# sVNS_16chan.net
KiCad netlist of a schematic drawn in EAGLE
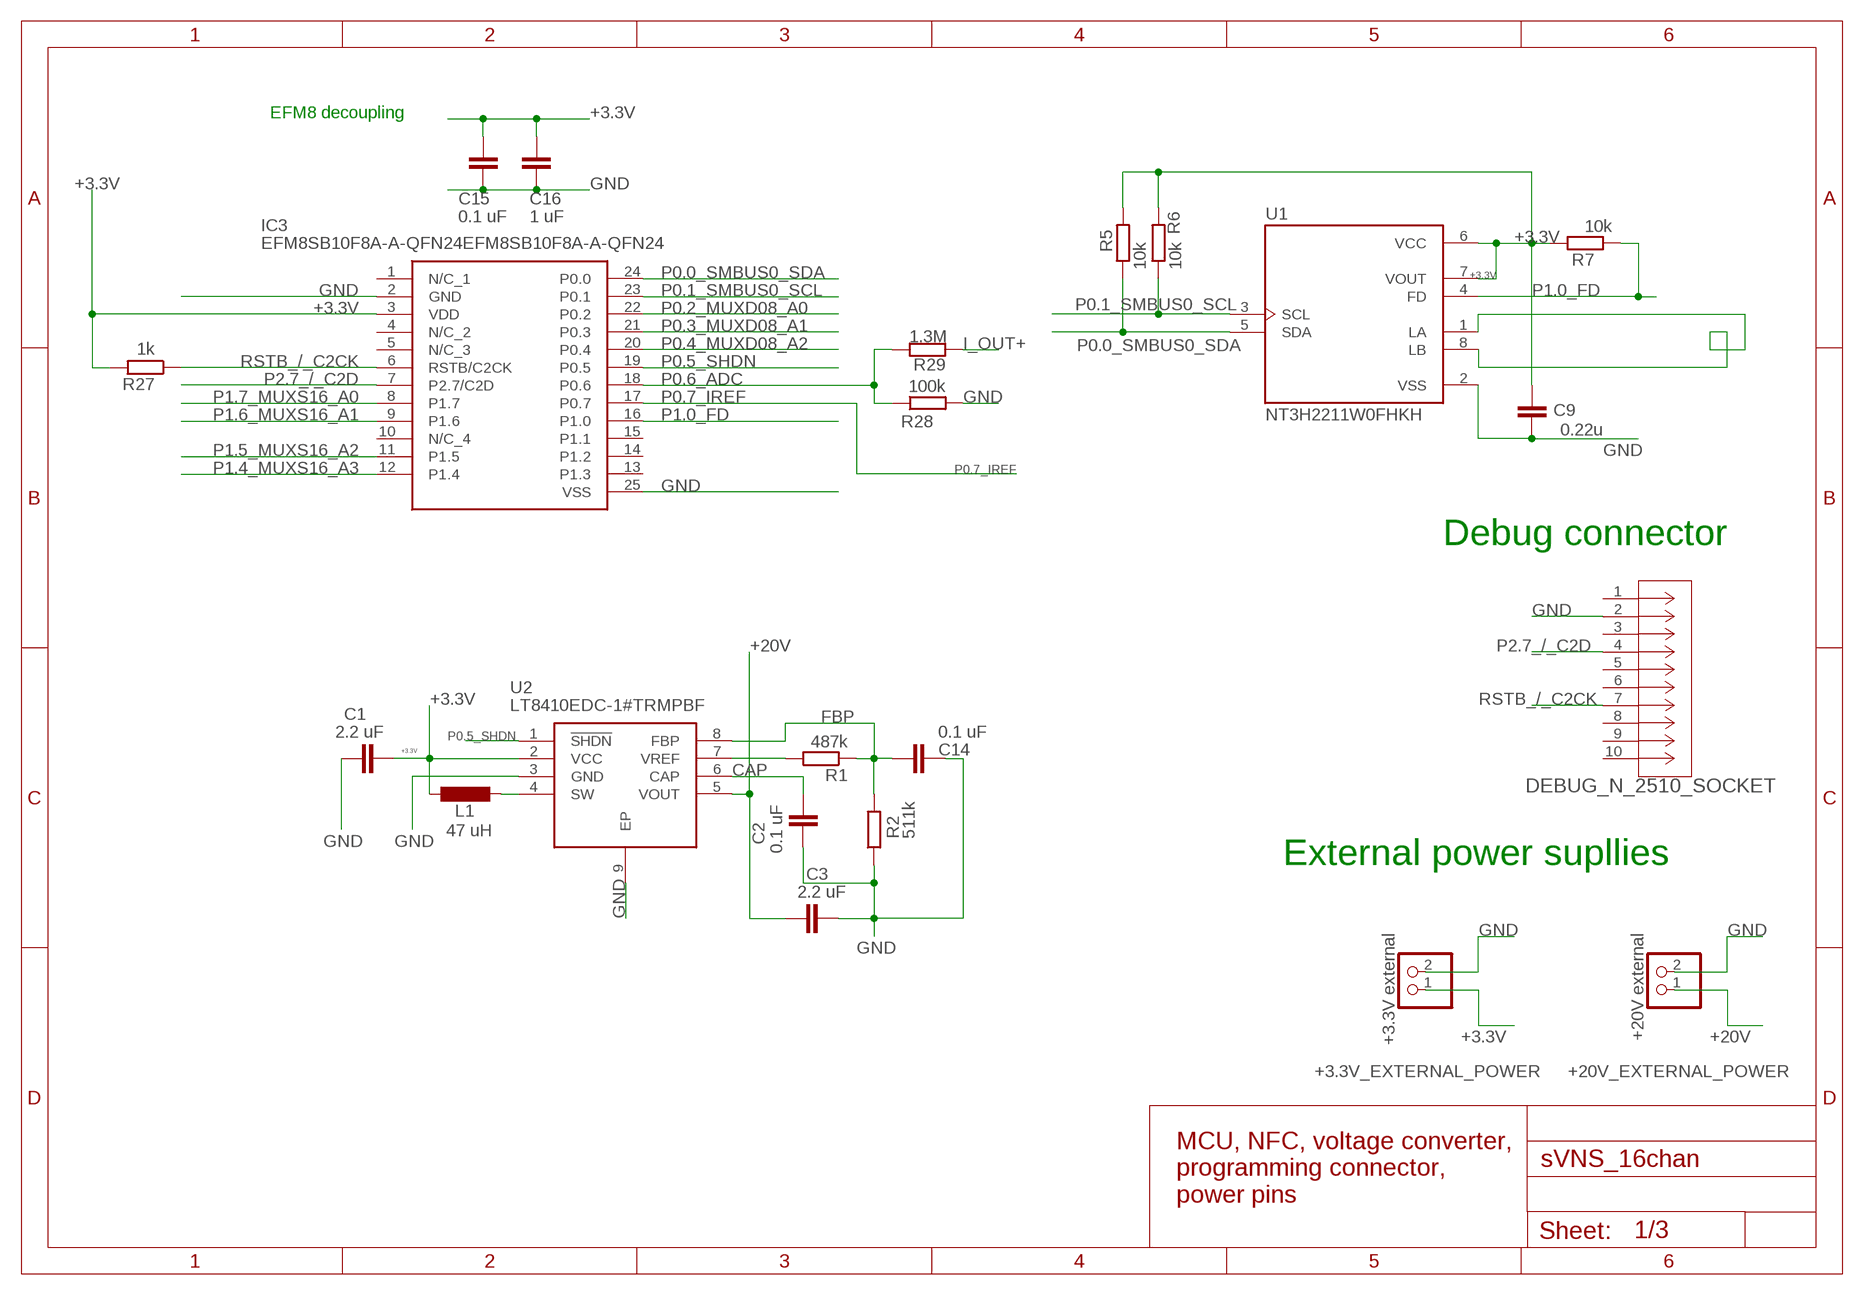
[diagram p0: schematic, sheet 1]
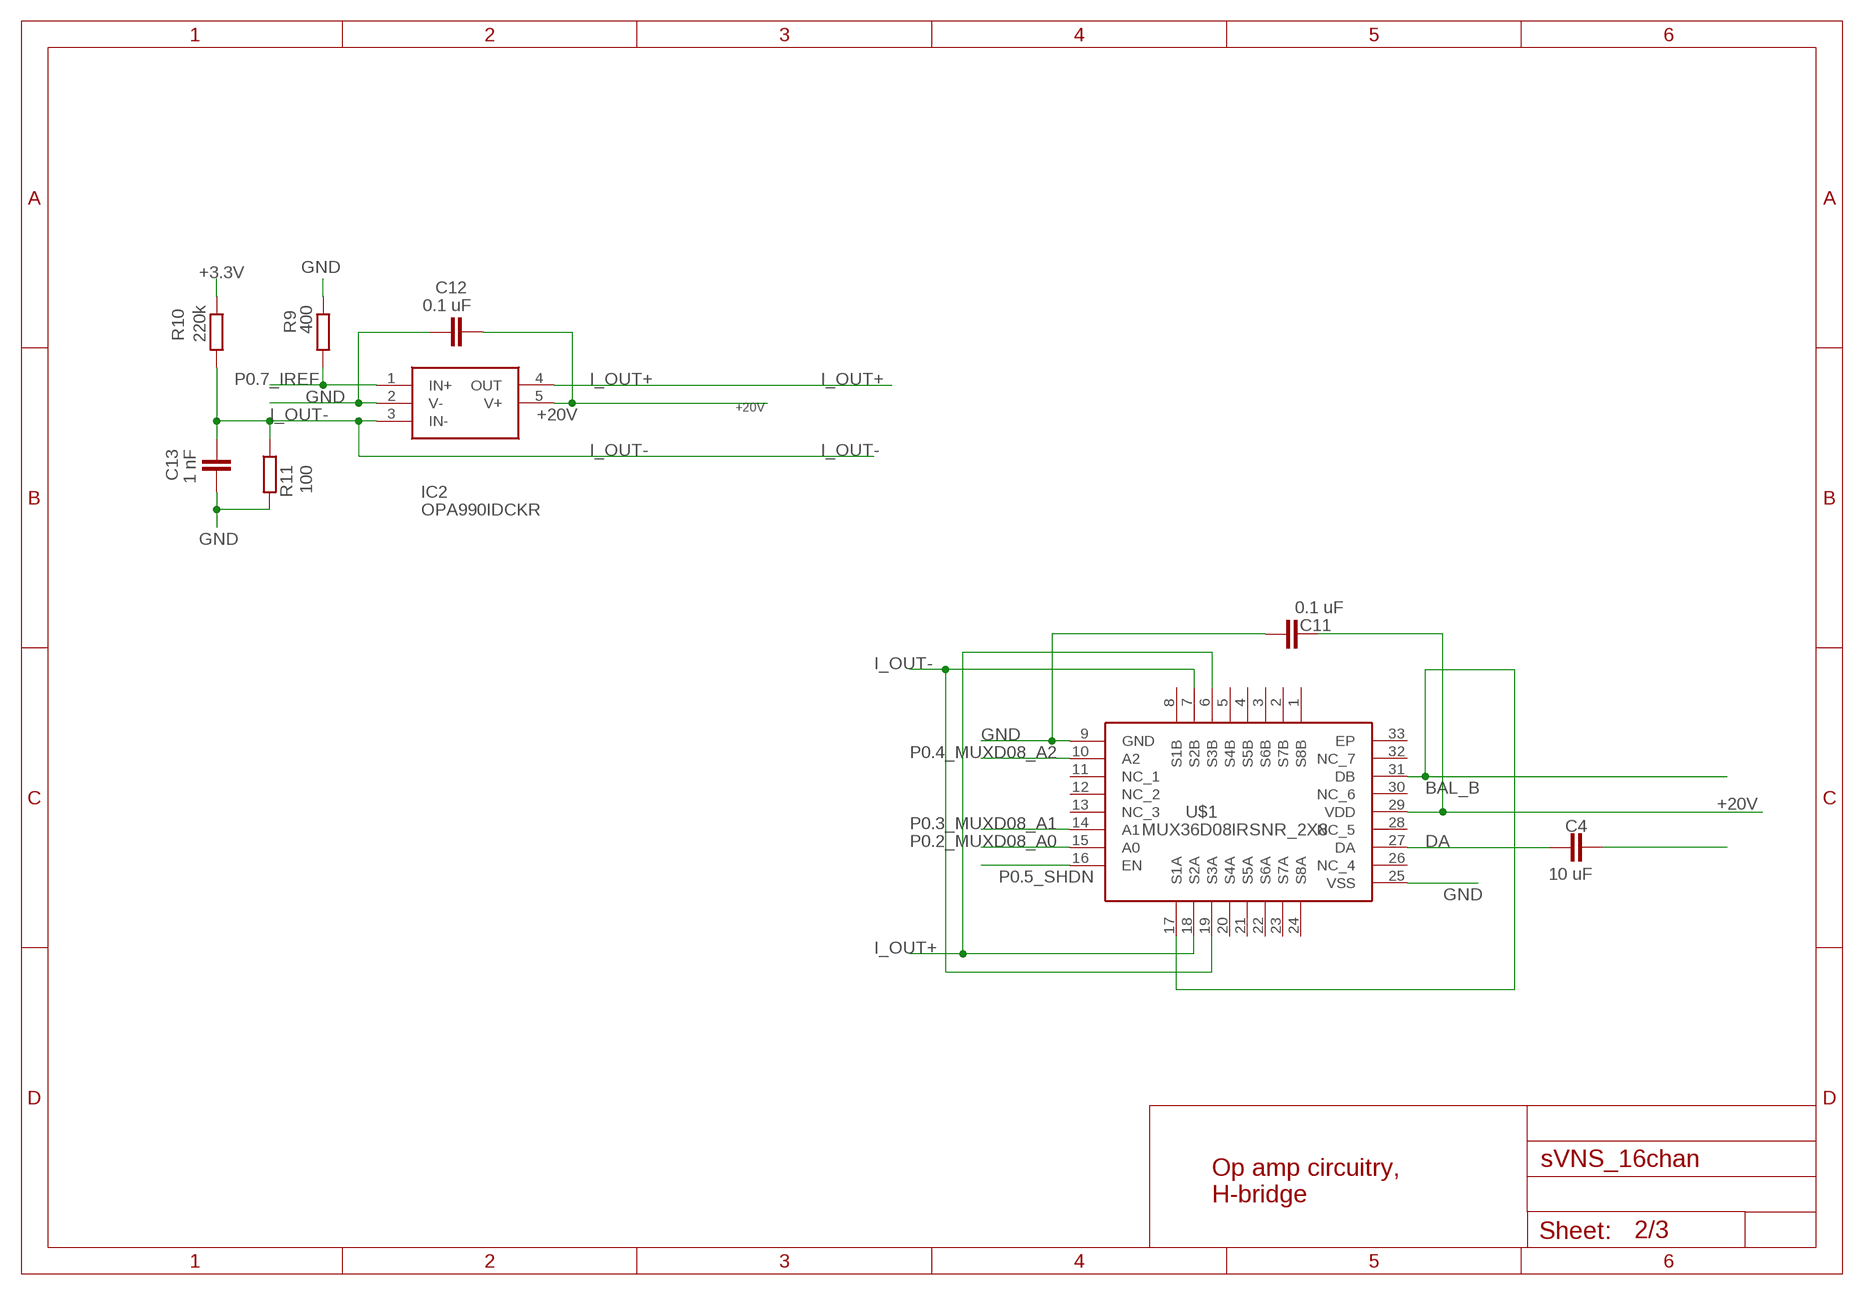
[diagram p1: schematic, sheet 2]
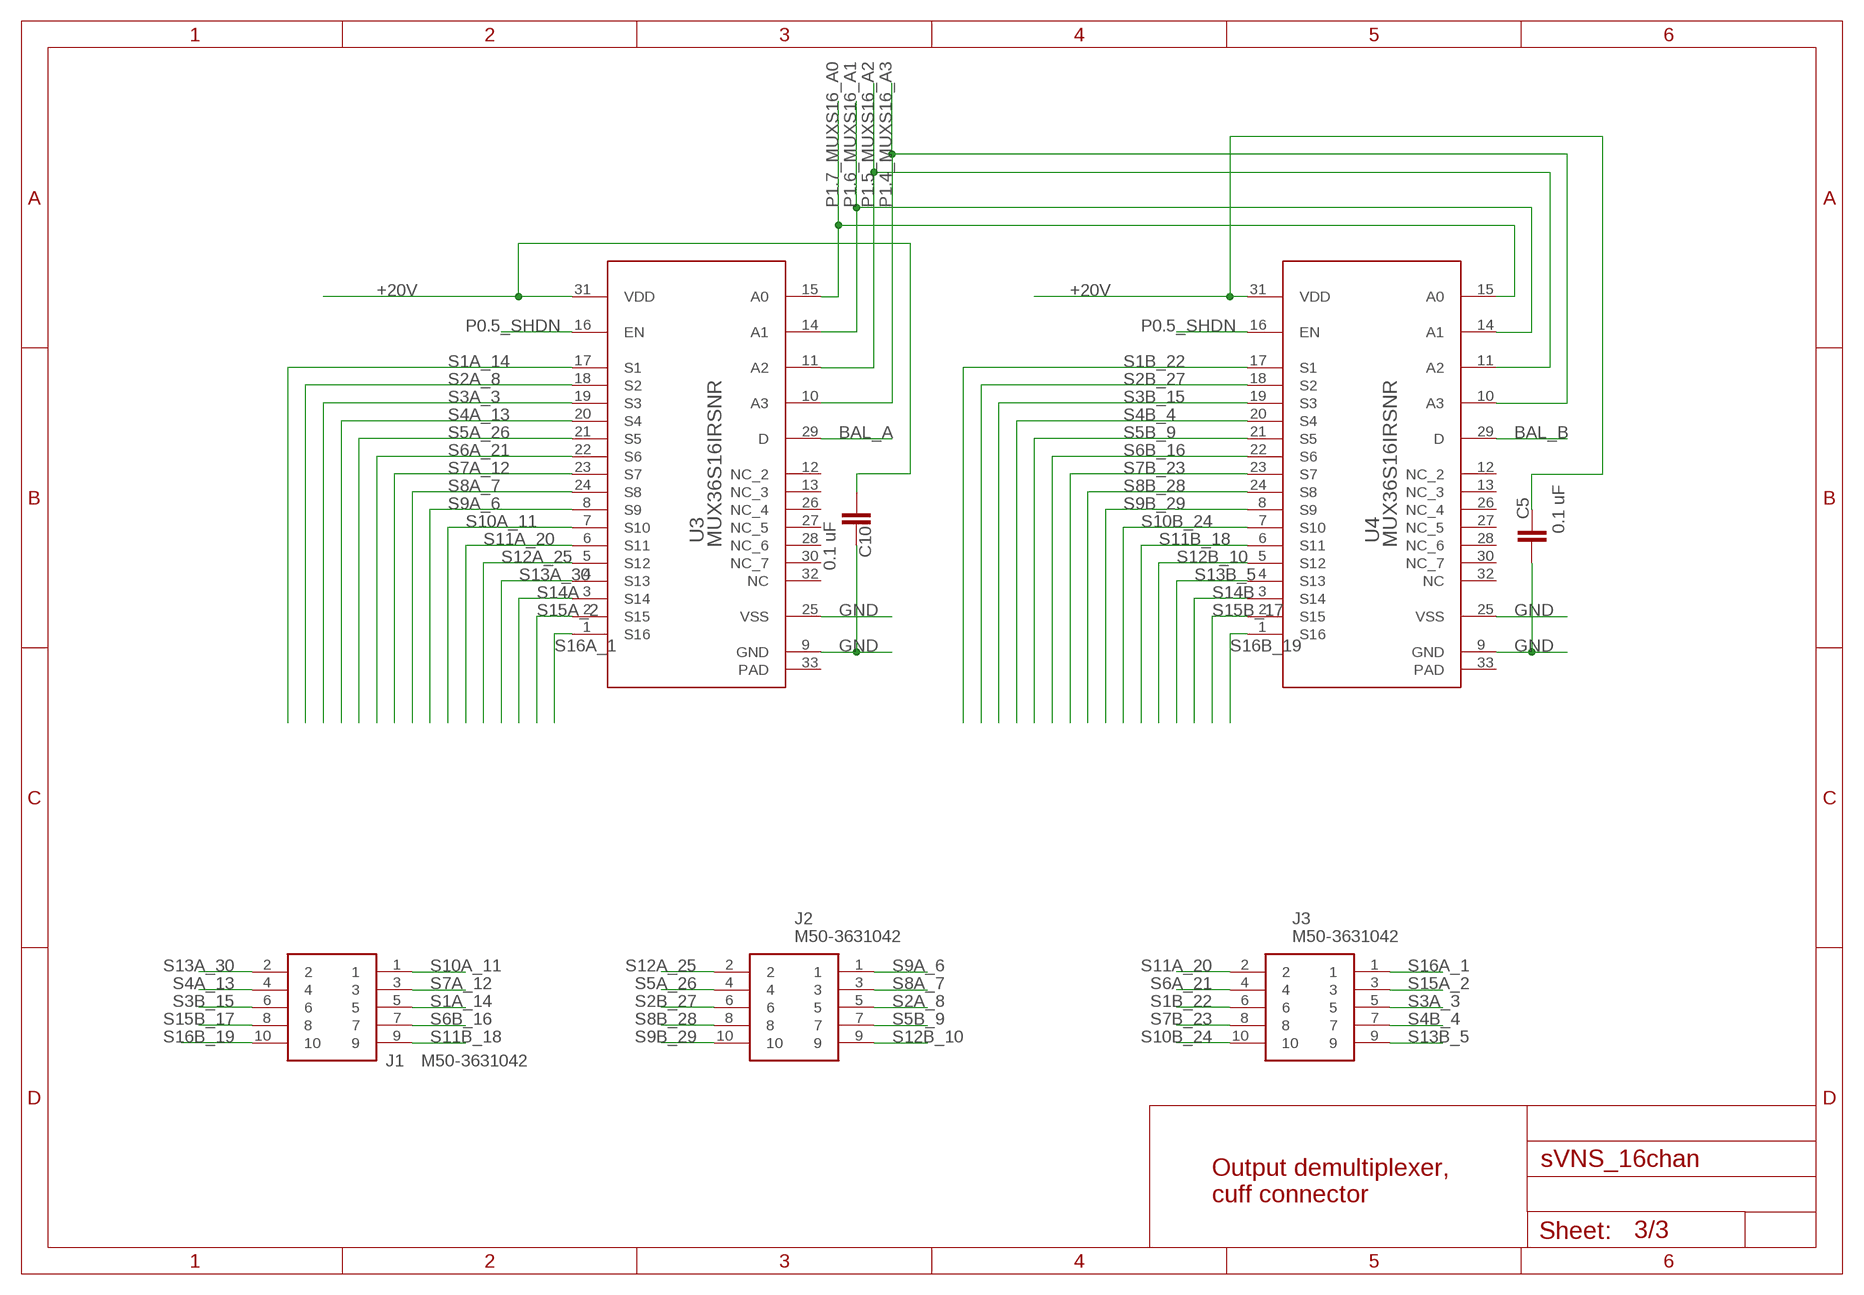
[diagram p2: schematic, sheet 3]

(export (version "E")
  (design (tool "Eeschema 10.0.6"))
  (components
    (comp (ref "C4")
      (value "10 uF")
      (footprint "eagle-import:C0603")
      (libsource (lib "eagle-import") (part "C-EUC0603"))
    )
    (comp (ref "C11")
      (value "0.1 uF")
      (footprint "eagle-import:C0603")
      (libsource (lib "eagle-import") (part "C-EUC0603"))
    )
    (comp (ref "C12")
      (value "0.1 uF")
      (footprint "eagle-import:C0603")
      (libsource (lib "eagle-import") (part "C-EUC0603"))
    )
    (comp (ref "C13")
      (value "1 nF")
      (footprint "eagle-import:C0603")
      (libsource (lib "eagle-import") (part "C-EUC0603"))
    )
    (comp (ref "IC2")
      (value "OPA990IDCKR")
      (footprint "eagle-import:SOT65P210X110-5N")
      (fields (field (name "MOUSER_PART_NUMBER") "595-OPA990IDCKR"))
      (libsource (lib "eagle-import") (part "OPA990IDCKR"))
    )
    (comp (ref "R9")
      (value "400")
      (footprint "eagle-import:R0603")
      (libsource (lib "eagle-import") (part "R-EU_R0603"))
    )
    (comp (ref "R10")
      (value "220k")
      (footprint "eagle-import:R0603")
      (libsource (lib "eagle-import") (part "R-EU_R0603"))
    )
    (comp (ref "R11")
      (value "100")
      (footprint "eagle-import:R0603")
      (libsource (lib "eagle-import") (part "R-EU_R0603"))
    )
    (comp (ref "U$1")
      (value "MUX36D08IRSNR_2X8")
      (footprint "eagle-import:QFN40P400X400X80-33N_2X8")
      (libsource (lib "eagle-import") (part "MUX36D08IRSNR_2X8"))
    )
    (comp (ref "+3.3V_EXTERNAL_POWER")
      (value "+3.3V external")
      (footprint "eagle-import:1X02")
      (libsource (lib "eagle-import") (part "PINHD-1X2"))
    )
    (comp (ref "+20V_EXTERNAL_POWER")
      (value "+20V external")
      (footprint "eagle-import:1X02")
      (libsource (lib "eagle-import") (part "PINHD-1X2"))
    )
    (comp (ref "C1")
      (value "2.2 uF")
      (footprint "eagle-import:C0603")
      (libsource (lib "eagle-import") (part "C-EUC0603"))
    )
    (comp (ref "C2")
      (value "0.1 uF")
      (footprint "eagle-import:C0603")
      (libsource (lib "eagle-import") (part "C-EUC0603"))
    )
    (comp (ref "C3")
      (value "2.2 uF")
      (footprint "eagle-import:C0603")
      (libsource (lib "eagle-import") (part "C-EUC0603"))
    )
    (comp (ref "C9")
      (value "0.22u")
      (footprint "eagle-import:C0603")
      (libsource (lib "eagle-import") (part "C-EUC0603"))
    )
    (comp (ref "C14")
      (value "0.1 uF")
      (footprint "eagle-import:C0603")
      (libsource (lib "eagle-import") (part "C-EUC0603"))
    )
    (comp (ref "C15")
      (value "0.1 uF")
      (footprint "eagle-import:C0603")
      (libsource (lib "eagle-import") (part "C-EUC0603"))
    )
    (comp (ref "C16")
      (value "1 uF")
      (footprint "eagle-import:C0603")
      (libsource (lib "eagle-import") (part "C-EUC0603"))
    )
    (comp (ref "DEBUG_N_2510_SOCKET")
      (value "N2510-6002RB")
      (footprint "eagle-import:CONN_6002RB_3MM")
      (fields (field (name "COPYRIGHT") "Copyright (C) 2021 Ultra Librarian. All rights reserved."))
      (libsource (lib "eagle-import") (part "N2510-6002RB"))
    )
    (comp (ref "IC3")
      (value "EFM8SB10F8A-A-QFN24EFM8SB10F8A-A-QFN24")
      (footprint "eagle-import:QFN50P400X400X80-25T245N")
      (libsource (lib "eagle-import") (part "EFM8SB10F8A-A-QFN24EFM8SB10F8A-A-QFN24"))
    )
    (comp (ref "L1")
      (value "47 uH")
      (footprint "eagle-import:0603PS-473KRC")
      (libsource (lib "eagle-import") (part "0603PS-473KRC0603PS"))
    )
    (comp (ref "R1")
      (value "487k")
      (footprint "eagle-import:R0603")
      (libsource (lib "eagle-import") (part "R-EU_R0603"))
    )
    (comp (ref "R2")
      (value "511k")
      (footprint "eagle-import:R0603")
      (libsource (lib "eagle-import") (part "R-EU_R0603"))
    )
    (comp (ref "R5")
      (value "10k")
      (footprint "eagle-import:R0603")
      (libsource (lib "eagle-import") (part "R-EU_R0603"))
    )
    (comp (ref "R6")
      (value "10k")
      (footprint "eagle-import:R0603")
      (libsource (lib "eagle-import") (part "R-EU_R0603"))
    )
    (comp (ref "R7")
      (value "10k")
      (footprint "eagle-import:R0603")
      (libsource (lib "eagle-import") (part "R-EU_R0603"))
    )
    (comp (ref "R27")
      (value "1k")
      (footprint "eagle-import:R0603")
      (libsource (lib "eagle-import") (part "R-EU_R0603"))
    )
    (comp (ref "R28")
      (value "100k")
      (footprint "eagle-import:R0603")
      (libsource (lib "eagle-import") (part "R-EU_R0603"))
    )
    (comp (ref "R29")
      (value "1.3M")
      (footprint "eagle-import:R0603")
      (libsource (lib "eagle-import") (part "R-EU_R0603"))
    )
    (comp (ref "U1")
      (value "NT3H2211W0FHKH")
      (footprint "eagle-import:IC_NT3H2211W0FHKH")
      (fields (field (name "MF") "NXP USA"))
      (libsource (lib "eagle-import") (part "NT3H2211W0FHKH"))
    )
    (comp (ref "U2")
      (value "LT8410EDC-1#TRMPBF")
      (footprint "eagle-import:SON45P200X200X80-9N")
      (fields (field (name "MOUSER_PART_NUMBER") "584-8410EDC-1TRMPBF"))
      (libsource (lib "eagle-import") (part "LT8410EDC-1#TRMPBF"))
    )
    (comp (ref "C5")
      (value "0.1 uF")
      (footprint "eagle-import:C0603")
      (libsource (lib "eagle-import") (part "C-EUC0603"))
    )
    (comp (ref "C10")
      (value "0.1 uF")
      (footprint "eagle-import:C0603")
      (libsource (lib "eagle-import") (part "C-EUC0603"))
    )
    (comp (ref "J1")
      (value "M50-3631042")
      (footprint "eagle-import:M503631042")
      (fields (field (name "MOUSER_PART_NUMBER") "855-M50-3631042"))
      (libsource (lib "eagle-import") (part "M50-3631042"))
    )
    (comp (ref "J2")
      (value "M50-3631042")
      (footprint "eagle-import:M503631042")
      (fields (field (name "MOUSER_PART_NUMBER") "855-M50-3631042"))
      (libsource (lib "eagle-import") (part "M50-3631042"))
    )
    (comp (ref "J3")
      (value "M50-3631042")
      (footprint "eagle-import:M503631042")
      (fields (field (name "MOUSER_PART_NUMBER") "855-M50-3631042"))
      (libsource (lib "eagle-import") (part "M50-3631042"))
    )
    (comp (ref "U3")
      (value "MUX36S16IRSNR")
      (footprint "eagle-import:RSN0032B")
      (fields (field (name "COPYRIGHT") "Copyright (C) 2022 Ultra Librarian. All rights reserved."))
      (libsource (lib "eagle-import") (part "MUX36S16IRSNR"))
    )
    (comp (ref "U4")
      (value "MUX36S16IRSNR")
      (footprint "eagle-import:RSN0032B")
      (fields (field (name "COPYRIGHT") "Copyright (C) 2022 Ultra Librarian. All rights reserved."))
      (libsource (lib "eagle-import") (part "MUX36S16IRSNR"))
    )
  )
  (nets
    (net (code "1") (name "+3.3V") (class "Default")
      (node (ref "+3.3V_EXTERNAL_POWER") (pin "1") (pinfunction "1_1") (pintype "passive"))
      (node (ref "C1") (pin "2") (pinfunction "2_2") (pintype "passive"))
      (node (ref "C15") (pin "2") (pinfunction "2_2") (pintype "passive"))
      (node (ref "C16") (pin "1") (pinfunction "1_1") (pintype "passive"))
      (node (ref "C9") (pin "1") (pinfunction "1_1") (pintype "passive"))
      (node (ref "IC3") (pin "3") (pinfunction "VDD_3") (pintype "power_in"))
      (node (ref "L1") (pin "P$1") (pinfunction "1_P$1") (pintype "passive"))
      (node (ref "R10") (pin "1") (pinfunction "1_1") (pintype "passive"))
      (node (ref "R27") (pin "2") (pinfunction "2_2") (pintype "passive"))
      (node (ref "R5") (pin "2") (pinfunction "2_2") (pintype "passive"))
      (node (ref "R6") (pin "2") (pinfunction "2_2") (pintype "passive"))
      (node (ref "R7") (pin "2") (pinfunction "2_2") (pintype "passive"))
      (node (ref "U1") (pin "6") (pinfunction "VCC_6") (pintype "power_in"))
      (node (ref "U1") (pin "7") (pinfunction "VOUT_7") (pintype "output"))
      (node (ref "U2") (pin "2") (pinfunction "VCC_2") (pintype "bidirectional"))
    )
    (net (code "2") (name "+20V") (class "Default")
      (node (ref "+20V_EXTERNAL_POWER") (pin "1") (pinfunction "1_1") (pintype "passive"))
      (node (ref "C10") (pin "1") (pinfunction "1_1") (pintype "passive"))
      (node (ref "C11") (pin "2") (pinfunction "2_2") (pintype "passive"))
      (node (ref "C12") (pin "1") (pinfunction "1_1") (pintype "passive"))
      (node (ref "C3") (pin "1") (pinfunction "1_1") (pintype "passive"))
      (node (ref "C5") (pin "2") (pinfunction "2_2") (pintype "passive"))
      (node (ref "IC2") (pin "5") (pinfunction "V+_5") (pintype "bidirectional"))
      (node (ref "U$1") (pin "29") (pinfunction "VDD_29") (pintype "bidirectional"))
      (node (ref "U2") (pin "5") (pinfunction "VOUT_5") (pintype "bidirectional"))
      (node (ref "U3") (pin "31") (pinfunction "VDD_31") (pintype "power_in"))
      (node (ref "U4") (pin "31") (pinfunction "VDD_31") (pintype "power_in"))
    )
    (net (code "3") (name "BAL_A") (class "Default")
      (node (ref "C4") (pin "2") (pinfunction "2_2") (pintype "passive"))
      (node (ref "U3") (pin "29") (pinfunction "D_29") (pintype "bidirectional"))
    )
    (net (code "4") (name "BAL_B") (class "Default")
      (node (ref "U$1") (pin "17") (pinfunction "S1A_17") (pintype "bidirectional"))
      (node (ref "U$1") (pin "31") (pinfunction "DB_31") (pintype "bidirectional"))
      (node (ref "U4") (pin "29") (pinfunction "D_29") (pintype "bidirectional"))
    )
    (net (code "5") (name "CAP") (class "Default")
      (node (ref "C2") (pin "2") (pinfunction "2_2") (pintype "passive"))
      (node (ref "U2") (pin "6") (pinfunction "CAP_6") (pintype "bidirectional"))
    )
    (net (code "6") (name "DA") (class "Default")
      (node (ref "C4") (pin "1") (pinfunction "1_1") (pintype "passive"))
      (node (ref "U$1") (pin "27") (pinfunction "DA_27") (pintype "bidirectional"))
    )
    (net (code "7") (name "FBP") (class "Default")
      (node (ref "C14") (pin "2") (pinfunction "2_2") (pintype "passive"))
      (node (ref "R1") (pin "1") (pinfunction "1_1") (pintype "passive"))
      (node (ref "R2") (pin "2") (pinfunction "2_2") (pintype "passive"))
      (node (ref "U2") (pin "8") (pinfunction "FBP_8") (pintype "bidirectional"))
    )
    (net (code "8") (name "GND") (class "Default")
      (node (ref "+20V_EXTERNAL_POWER") (pin "2") (pinfunction "2_2") (pintype "passive"))
      (node (ref "+3.3V_EXTERNAL_POWER") (pin "2") (pinfunction "2_2") (pintype "passive"))
      (node (ref "C1") (pin "1") (pinfunction "1_1") (pintype "passive"))
      (node (ref "C10") (pin "2") (pinfunction "2_2") (pintype "passive"))
      (node (ref "C11") (pin "1") (pinfunction "1_1") (pintype "passive"))
      (node (ref "C12") (pin "2") (pinfunction "2_2") (pintype "passive"))
      (node (ref "C13") (pin "1") (pinfunction "1_1") (pintype "passive"))
      (node (ref "C14") (pin "1") (pinfunction "1_1") (pintype "passive"))
      (node (ref "C15") (pin "1") (pinfunction "1_1") (pintype "passive"))
      (node (ref "C16") (pin "2") (pinfunction "2_2") (pintype "passive"))
      (node (ref "C2") (pin "1") (pinfunction "1_1") (pintype "passive"))
      (node (ref "C3") (pin "2") (pinfunction "2_2") (pintype "passive"))
      (node (ref "C5") (pin "1") (pinfunction "1_1") (pintype "passive"))
      (node (ref "C9") (pin "2") (pinfunction "2_2") (pintype "passive"))
      (node (ref "DEBUG_N_2510_SOCKET") (pin "2") (pinfunction "2_2") (pintype "passive"))
      (node (ref "IC2") (pin "2") (pinfunction "V-_2") (pintype "bidirectional"))
      (node (ref "IC3") (pin "2") (pinfunction "GND_2") (pintype "bidirectional"))
      (node (ref "IC3") (pin "25") (pinfunction "VSS_25") (pintype "bidirectional"))
      (node (ref "R11") (pin "2") (pinfunction "2_2") (pintype "passive"))
      (node (ref "R2") (pin "1") (pinfunction "1_1") (pintype "passive"))
      (node (ref "R28") (pin "2") (pinfunction "2_2") (pintype "passive"))
      (node (ref "R9") (pin "1") (pinfunction "1_1") (pintype "passive"))
      (node (ref "U$1") (pin "25") (pinfunction "VSS_25") (pintype "bidirectional"))
      (node (ref "U$1") (pin "9") (pinfunction "GND_9") (pintype "bidirectional"))
      (node (ref "U1") (pin "2") (pinfunction "VSS_2") (pintype "power_in"))
      (node (ref "U2") (pin "3") (pinfunction "GND_3") (pintype "bidirectional"))
      (node (ref "U2") (pin "9") (pinfunction "EP_9") (pintype "bidirectional"))
      (node (ref "U3") (pin "25") (pinfunction "VSS_25") (pintype "power_in"))
      (node (ref "U3") (pin "9") (pinfunction "GND_9") (pintype "power_in"))
      (node (ref "U4") (pin "25") (pinfunction "VSS_25") (pintype "power_in"))
      (node (ref "U4") (pin "9") (pinfunction "GND_9") (pintype "power_in"))
    )
    (net (code "9") (name "I_OUT+") (class "Default")
      (node (ref "IC2") (pin "4") (pinfunction "OUT_4") (pintype "bidirectional"))
      (node (ref "R29") (pin "1") (pinfunction "1_1") (pintype "passive"))
      (node (ref "U$1") (pin "18") (pinfunction "S2A_18") (pintype "bidirectional"))
      (node (ref "U$1") (pin "6") (pinfunction "S3B_6") (pintype "bidirectional"))
    )
    (net (code "10") (name "I_OUT-") (class "Default")
      (node (ref "C13") (pin "2") (pinfunction "2_2") (pintype "passive"))
      (node (ref "IC2") (pin "3") (pinfunction "IN-_3") (pintype "bidirectional"))
      (node (ref "R10") (pin "2") (pinfunction "2_2") (pintype "passive"))
      (node (ref "R11") (pin "1") (pinfunction "1_1") (pintype "passive"))
      (node (ref "U$1") (pin "19") (pinfunction "S3A_19") (pintype "bidirectional"))
      (node (ref "U$1") (pin "7") (pinfunction "S2B_7") (pintype "bidirectional"))
    )
    (net (code "11") (name "Net-(L1-2)") (class "Default")
      (node (ref "L1") (pin "P$2") (pinfunction "2_P$2") (pintype "passive"))
      (node (ref "U2") (pin "4") (pinfunction "SW_4") (pintype "bidirectional"))
    )
    (net (code "12") (name "Net-(U1-LA)") (class "Default")
      (node (ref "U1") (pin "1") (pinfunction "LA_1") (pintype "bidirectional"))
      (node (ref "U1") (pin "8") (pinfunction "LB_8") (pintype "bidirectional"))
    )
    (net (code "13") (name "Net-(U2-VREF)") (class "Default")
      (node (ref "R1") (pin "2") (pinfunction "2_2") (pintype "passive"))
      (node (ref "U2") (pin "7") (pinfunction "VREF_7") (pintype "bidirectional"))
    )
    (net (code "14") (name "P0.0_SMBUS0_SDA") (class "Default")
      (node (ref "IC3") (pin "24") (pinfunction "P0.0_24") (pintype "bidirectional"))
      (node (ref "R5") (pin "1") (pinfunction "1_1") (pintype "passive"))
      (node (ref "U1") (pin "5") (pinfunction "SDA_5") (pintype "bidirectional"))
    )
    (net (code "15") (name "P0.1_SMBUS0_SCL") (class "Default")
      (node (ref "IC3") (pin "23") (pinfunction "P0.1_23") (pintype "bidirectional"))
      (node (ref "R6") (pin "1") (pinfunction "1_1") (pintype "passive"))
      (node (ref "U1") (pin "3") (pinfunction "SCL_3") (pintype "input"))
    )
    (net (code "16") (name "P0.2_MUXD08_A0") (class "Default")
      (node (ref "IC3") (pin "22") (pinfunction "P0.2_22") (pintype "bidirectional"))
      (node (ref "U$1") (pin "15") (pinfunction "A0_15") (pintype "bidirectional"))
    )
    (net (code "17") (name "P0.3_MUXD08_A1") (class "Default")
      (node (ref "IC3") (pin "21") (pinfunction "P0.3_21") (pintype "bidirectional"))
      (node (ref "U$1") (pin "14") (pinfunction "A1_14") (pintype "bidirectional"))
    )
    (net (code "18") (name "P0.4_MUXD08_A2") (class "Default")
      (node (ref "IC3") (pin "20") (pinfunction "P0.4_20") (pintype "bidirectional"))
      (node (ref "U$1") (pin "10") (pinfunction "A2_10") (pintype "bidirectional"))
    )
    (net (code "19") (name "P0.5_SHDN") (class "Default")
      (node (ref "IC3") (pin "19") (pinfunction "P0.5_19") (pintype "bidirectional"))
      (node (ref "U$1") (pin "16") (pinfunction "EN_16") (pintype "bidirectional"))
      (node (ref "U2") (pin "1") (pinfunction "~{SHDN}_1") (pintype "bidirectional"))
      (node (ref "U3") (pin "16") (pinfunction "EN_16") (pintype "input"))
      (node (ref "U4") (pin "16") (pinfunction "EN_16") (pintype "input"))
    )
    (net (code "20") (name "P0.6_ADC") (class "Default")
      (node (ref "IC3") (pin "18") (pinfunction "P0.6_18") (pintype "bidirectional"))
      (node (ref "R28") (pin "1") (pinfunction "1_1") (pintype "passive"))
      (node (ref "R29") (pin "2") (pinfunction "2_2") (pintype "passive"))
    )
    (net (code "21") (name "P0.7_IREF") (class "Default")
      (node (ref "IC2") (pin "1") (pinfunction "IN+_1") (pintype "bidirectional"))
      (node (ref "IC3") (pin "17") (pinfunction "P0.7_17") (pintype "bidirectional"))
      (node (ref "R9") (pin "2") (pinfunction "2_2") (pintype "passive"))
    )
    (net (code "22") (name "P1.0_FD") (class "Default")
      (node (ref "IC3") (pin "16") (pinfunction "P1.0_16") (pintype "bidirectional"))
      (node (ref "R7") (pin "1") (pinfunction "1_1") (pintype "passive"))
      (node (ref "U1") (pin "4") (pinfunction "FD_4") (pintype "output"))
    )
    (net (code "23") (name "P1.4_MUXS16_A3") (class "Default")
      (node (ref "IC3") (pin "12") (pinfunction "P1.4_12") (pintype "bidirectional"))
      (node (ref "U3") (pin "10") (pinfunction "A3_10") (pintype "input"))
      (node (ref "U4") (pin "10") (pinfunction "A3_10") (pintype "input"))
    )
    (net (code "24") (name "P1.5_MUXS16_A2") (class "Default")
      (node (ref "IC3") (pin "11") (pinfunction "P1.5_11") (pintype "bidirectional"))
      (node (ref "U3") (pin "11") (pinfunction "A2_11") (pintype "input"))
      (node (ref "U4") (pin "11") (pinfunction "A2_11") (pintype "input"))
    )
    (net (code "25") (name "P1.6_MUXS16_A1") (class "Default")
      (node (ref "IC3") (pin "9") (pinfunction "P1.6_9") (pintype "bidirectional"))
      (node (ref "U3") (pin "14") (pinfunction "A1_14") (pintype "input"))
      (node (ref "U4") (pin "14") (pinfunction "A1_14") (pintype "input"))
    )
    (net (code "26") (name "P1.7_MUXS16_A0") (class "Default")
      (node (ref "IC3") (pin "8") (pinfunction "P1.7_8") (pintype "bidirectional"))
      (node (ref "U3") (pin "15") (pinfunction "A0_15") (pintype "input"))
      (node (ref "U4") (pin "15") (pinfunction "A0_15") (pintype "input"))
    )
    (net (code "27") (name "P2.7_{slash}_C2D") (class "Default")
      (node (ref "DEBUG_N_2510_SOCKET") (pin "4") (pinfunction "4_4") (pintype "passive"))
      (node (ref "IC3") (pin "7") (pinfunction "P2.7/C2D_7") (pintype "bidirectional"))
    )
    (net (code "28") (name "RSTB_{slash}_C2CK") (class "Default")
      (node (ref "DEBUG_N_2510_SOCKET") (pin "7") (pinfunction "7_7") (pintype "passive"))
      (node (ref "IC3") (pin "6") (pinfunction "RSTB/C2CK_6") (pintype "bidirectional"))
      (node (ref "R27") (pin "1") (pinfunction "1_1") (pintype "passive"))
    )
    (net (code "29") (name "S1A_14") (class "Default")
      (node (ref "J1") (pin "5") (pinfunction "5_5") (pintype "bidirectional"))
      (node (ref "U3") (pin "17") (pinfunction "S1_17") (pintype "bidirectional"))
    )
    (net (code "30") (name "S1B_22") (class "Default")
      (node (ref "J3") (pin "6") (pinfunction "6_6") (pintype "bidirectional"))
      (node (ref "U4") (pin "17") (pinfunction "S1_17") (pintype "bidirectional"))
    )
    (net (code "31") (name "S2A_8") (class "Default")
      (node (ref "J2") (pin "5") (pinfunction "5_5") (pintype "bidirectional"))
      (node (ref "U3") (pin "18") (pinfunction "S2_18") (pintype "bidirectional"))
    )
    (net (code "32") (name "S2B_27") (class "Default")
      (node (ref "J2") (pin "6") (pinfunction "6_6") (pintype "bidirectional"))
      (node (ref "U4") (pin "18") (pinfunction "S2_18") (pintype "bidirectional"))
    )
    (net (code "33") (name "S3A_3") (class "Default")
      (node (ref "J3") (pin "5") (pinfunction "5_5") (pintype "bidirectional"))
      (node (ref "U3") (pin "19") (pinfunction "S3_19") (pintype "bidirectional"))
    )
    (net (code "34") (name "S3B_15") (class "Default")
      (node (ref "J1") (pin "6") (pinfunction "6_6") (pintype "bidirectional"))
      (node (ref "U4") (pin "19") (pinfunction "S3_19") (pintype "bidirectional"))
    )
    (net (code "35") (name "S4A_13") (class "Default")
      (node (ref "J1") (pin "4") (pinfunction "4_4") (pintype "bidirectional"))
      (node (ref "U3") (pin "20") (pinfunction "S4_20") (pintype "bidirectional"))
    )
    (net (code "36") (name "S4B_4") (class "Default")
      (node (ref "J3") (pin "7") (pinfunction "7_7") (pintype "bidirectional"))
      (node (ref "U4") (pin "20") (pinfunction "S4_20") (pintype "bidirectional"))
    )
    (net (code "37") (name "S5A_26") (class "Default")
      (node (ref "J2") (pin "4") (pinfunction "4_4") (pintype "bidirectional"))
      (node (ref "U3") (pin "21") (pinfunction "S5_21") (pintype "bidirectional"))
    )
    (net (code "38") (name "S5B_9") (class "Default")
      (node (ref "J2") (pin "7") (pinfunction "7_7") (pintype "bidirectional"))
      (node (ref "U4") (pin "21") (pinfunction "S5_21") (pintype "bidirectional"))
    )
    (net (code "39") (name "S6A_21") (class "Default")
      (node (ref "J3") (pin "4") (pinfunction "4_4") (pintype "bidirectional"))
      (node (ref "U3") (pin "22") (pinfunction "S6_22") (pintype "bidirectional"))
    )
    (net (code "40") (name "S6B_16") (class "Default")
      (node (ref "J1") (pin "7") (pinfunction "7_7") (pintype "bidirectional"))
      (node (ref "U4") (pin "22") (pinfunction "S6_22") (pintype "bidirectional"))
    )
    (net (code "41") (name "S7A_12") (class "Default")
      (node (ref "J1") (pin "3") (pinfunction "3_3") (pintype "bidirectional"))
      (node (ref "U3") (pin "23") (pinfunction "S7_23") (pintype "bidirectional"))
    )
    (net (code "42") (name "S7B_23") (class "Default")
      (node (ref "J3") (pin "8") (pinfunction "8_8") (pintype "bidirectional"))
      (node (ref "U4") (pin "23") (pinfunction "S7_23") (pintype "bidirectional"))
    )
    (net (code "43") (name "S8A_7") (class "Default")
      (node (ref "J2") (pin "3") (pinfunction "3_3") (pintype "bidirectional"))
      (node (ref "U3") (pin "24") (pinfunction "S8_24") (pintype "bidirectional"))
    )
    (net (code "44") (name "S8B_28") (class "Default")
      (node (ref "J2") (pin "8") (pinfunction "8_8") (pintype "bidirectional"))
      (node (ref "U4") (pin "24") (pinfunction "S8_24") (pintype "bidirectional"))
    )
    (net (code "45") (name "S9A_6") (class "Default")
      (node (ref "J2") (pin "1") (pinfunction "1_1") (pintype "bidirectional"))
      (node (ref "U3") (pin "8") (pinfunction "S9_8") (pintype "bidirectional"))
    )
    (net (code "46") (name "S9B_29") (class "Default")
      (node (ref "J2") (pin "10") (pinfunction "10_10") (pintype "bidirectional"))
      (node (ref "U4") (pin "8") (pinfunction "S9_8") (pintype "bidirectional"))
    )
    (net (code "47") (name "S10A_11") (class "Default")
      (node (ref "J1") (pin "1") (pinfunction "1_1") (pintype "bidirectional"))
      (node (ref "U3") (pin "7") (pinfunction "S10_7") (pintype "bidirectional"))
    )
    (net (code "48") (name "S10B_24") (class "Default")
      (node (ref "J3") (pin "10") (pinfunction "10_10") (pintype "bidirectional"))
      (node (ref "U4") (pin "7") (pinfunction "S10_7") (pintype "bidirectional"))
    )
    (net (code "49") (name "S11A_20") (class "Default")
      (node (ref "J3") (pin "2") (pinfunction "2_2") (pintype "bidirectional"))
      (node (ref "U3") (pin "6") (pinfunction "S11_6") (pintype "bidirectional"))
    )
    (net (code "50") (name "S11B_18") (class "Default")
      (node (ref "J1") (pin "9") (pinfunction "9_9") (pintype "bidirectional"))
      (node (ref "U4") (pin "6") (pinfunction "S11_6") (pintype "bidirectional"))
    )
    (net (code "51") (name "S12A_25") (class "Default")
      (node (ref "J2") (pin "2") (pinfunction "2_2") (pintype "bidirectional"))
      (node (ref "U3") (pin "5") (pinfunction "S12_5") (pintype "bidirectional"))
    )
    (net (code "52") (name "S12B_10") (class "Default")
      (node (ref "J2") (pin "9") (pinfunction "9_9") (pintype "bidirectional"))
      (node (ref "U4") (pin "5") (pinfunction "S12_5") (pintype "bidirectional"))
    )
    (net (code "53") (name "S13A_30") (class "Default")
      (node (ref "J1") (pin "2") (pinfunction "2_2") (pintype "bidirectional"))
      (node (ref "U3") (pin "4") (pinfunction "S13_4") (pintype "bidirectional"))
    )
    (net (code "54") (name "S13B_5") (class "Default")
      (node (ref "J3") (pin "9") (pinfunction "9_9") (pintype "bidirectional"))
      (node (ref "U4") (pin "4") (pinfunction "S13_4") (pintype "bidirectional"))
    )
    (net (code "55") (name "S14A") (class "Default")
      (node (ref "U3") (pin "3") (pinfunction "S14_3") (pintype "bidirectional"))
    )
    (net (code "56") (name "S14B") (class "Default")
      (node (ref "U4") (pin "3") (pinfunction "S14_3") (pintype "bidirectional"))
    )
    (net (code "57") (name "S15A_2") (class "Default")
      (node (ref "J3") (pin "3") (pinfunction "3_3") (pintype "bidirectional"))
      (node (ref "U3") (pin "2") (pinfunction "S15_2") (pintype "bidirectional"))
    )
    (net (code "58") (name "S15B_17") (class "Default")
      (node (ref "J1") (pin "8") (pinfunction "8_8") (pintype "bidirectional"))
      (node (ref "U4") (pin "2") (pinfunction "S15_2") (pintype "bidirectional"))
    )
    (net (code "59") (name "S16A_1") (class "Default")
      (node (ref "J3") (pin "1") (pinfunction "1_1") (pintype "bidirectional"))
      (node (ref "U3") (pin "1") (pinfunction "S16_1") (pintype "bidirectional"))
    )
    (net (code "60") (name "S16B_19") (class "Default")
      (node (ref "J1") (pin "10") (pinfunction "10_10") (pintype "bidirectional"))
      (node (ref "U4") (pin "1") (pinfunction "S16_1") (pintype "bidirectional"))
    )
    (net (code "61") (name "unconnected-(DEBUG_N_2510_SOCKET-Pad1)") (class "Default")
      (node (ref "DEBUG_N_2510_SOCKET") (pin "1") (pinfunction "1_1") (pintype "passive"))
    )
    (net (code "62") (name "unconnected-(DEBUG_N_2510_SOCKET-Pad3)") (class "Default")
      (node (ref "DEBUG_N_2510_SOCKET") (pin "3") (pinfunction "3_3") (pintype "passive"))
    )
    (net (code "63") (name "unconnected-(DEBUG_N_2510_SOCKET-Pad5)") (class "Default")
      (node (ref "DEBUG_N_2510_SOCKET") (pin "5") (pinfunction "5_5") (pintype "passive"))
    )
    (net (code "64") (name "unconnected-(DEBUG_N_2510_SOCKET-Pad6)") (class "Default")
      (node (ref "DEBUG_N_2510_SOCKET") (pin "6") (pinfunction "6_6") (pintype "passive"))
    )
    (net (code "65") (name "unconnected-(DEBUG_N_2510_SOCKET-Pad8)") (class "Default")
      (node (ref "DEBUG_N_2510_SOCKET") (pin "8") (pinfunction "8_8") (pintype "passive"))
    )
    (net (code "66") (name "unconnected-(DEBUG_N_2510_SOCKET-Pad9)") (class "Default")
      (node (ref "DEBUG_N_2510_SOCKET") (pin "9") (pinfunction "9_9") (pintype "passive"))
    )
    (net (code "67") (name "unconnected-(DEBUG_N_2510_SOCKET-Pad10)") (class "Default")
      (node (ref "DEBUG_N_2510_SOCKET") (pin "10") (pinfunction "10_10") (pintype "passive"))
    )
    (net (code "68") (name "unconnected-(IC3-N{slash}C_1-Pad1)") (class "Default")
      (node (ref "IC3") (pin "1") (pinfunction "N/C_1_1") (pintype "no_connect"))
    )
    (net (code "69") (name "unconnected-(IC3-N{slash}C_2-Pad4)") (class "Default")
      (node (ref "IC3") (pin "4") (pinfunction "N/C_2_4") (pintype "no_connect"))
    )
    (net (code "70") (name "unconnected-(IC3-N{slash}C_3-Pad5)") (class "Default")
      (node (ref "IC3") (pin "5") (pinfunction "N/C_3_5") (pintype "no_connect"))
    )
    (net (code "71") (name "unconnected-(IC3-N{slash}C_4-Pad10)") (class "Default")
      (node (ref "IC3") (pin "10") (pinfunction "N/C_4_10") (pintype "no_connect"))
    )
    (net (code "72") (name "unconnected-(IC3-P1.1-Pad15)") (class "Default")
      (node (ref "IC3") (pin "15") (pinfunction "P1.1_15") (pintype "bidirectional"))
    )
    (net (code "73") (name "unconnected-(IC3-P1.2-Pad14)") (class "Default")
      (node (ref "IC3") (pin "14") (pinfunction "P1.2_14") (pintype "bidirectional"))
    )
    (net (code "74") (name "unconnected-(IC3-P1.3-Pad13)") (class "Default")
      (node (ref "IC3") (pin "13") (pinfunction "P1.3_13") (pintype "bidirectional"))
    )
    (net (code "75") (name "unconnected-(U$1-EP-Pad33)") (class "Default")
      (node (ref "U$1") (pin "33") (pinfunction "EP_33") (pintype "bidirectional"))
    )
    (net (code "76") (name "unconnected-(U$1-NC_1-Pad11)") (class "Default")
      (node (ref "U$1") (pin "11") (pinfunction "NC_1_11") (pintype "bidirectional"))
    )
    (net (code "77") (name "unconnected-(U$1-NC_2-Pad12)") (class "Default")
      (node (ref "U$1") (pin "12") (pinfunction "NC_2_12") (pintype "bidirectional"))
    )
    (net (code "78") (name "unconnected-(U$1-NC_3-Pad13)") (class "Default")
      (node (ref "U$1") (pin "13") (pinfunction "NC_3_13") (pintype "bidirectional"))
    )
    (net (code "79") (name "unconnected-(U$1-NC_4-Pad26)") (class "Default")
      (node (ref "U$1") (pin "26") (pinfunction "NC_4_26") (pintype "bidirectional"))
    )
    (net (code "80") (name "unconnected-(U$1-NC_5-Pad28)") (class "Default")
      (node (ref "U$1") (pin "28") (pinfunction "NC_5_28") (pintype "bidirectional"))
    )
    (net (code "81") (name "unconnected-(U$1-NC_6-Pad30)") (class "Default")
      (node (ref "U$1") (pin "30") (pinfunction "NC_6_30") (pintype "bidirectional"))
    )
    (net (code "82") (name "unconnected-(U$1-NC_7-Pad32)") (class "Default")
      (node (ref "U$1") (pin "32") (pinfunction "NC_7_32") (pintype "bidirectional"))
    )
    (net (code "83") (name "unconnected-(U$1-S1B-Pad8)") (class "Default")
      (node (ref "U$1") (pin "8") (pinfunction "S1B_8") (pintype "bidirectional"))
    )
    (net (code "84") (name "unconnected-(U$1-S4A-Pad20)") (class "Default")
      (node (ref "U$1") (pin "20") (pinfunction "S4A_20") (pintype "bidirectional"))
    )
    (net (code "85") (name "unconnected-(U$1-S4B-Pad5)") (class "Default")
      (node (ref "U$1") (pin "5") (pinfunction "S4B_5") (pintype "bidirectional"))
    )
    (net (code "86") (name "unconnected-(U$1-S5A-Pad21)") (class "Default")
      (node (ref "U$1") (pin "21") (pinfunction "S5A_21") (pintype "bidirectional"))
    )
    (net (code "87") (name "unconnected-(U$1-S5B-Pad4)") (class "Default")
      (node (ref "U$1") (pin "4") (pinfunction "S5B_4") (pintype "bidirectional"))
    )
    (net (code "88") (name "unconnected-(U$1-S6A-Pad22)") (class "Default")
      (node (ref "U$1") (pin "22") (pinfunction "S6A_22") (pintype "bidirectional"))
    )
    (net (code "89") (name "unconnected-(U$1-S6B-Pad3)") (class "Default")
      (node (ref "U$1") (pin "3") (pinfunction "S6B_3") (pintype "bidirectional"))
    )
    (net (code "90") (name "unconnected-(U$1-S7A-Pad23)") (class "Default")
      (node (ref "U$1") (pin "23") (pinfunction "S7A_23") (pintype "bidirectional"))
    )
    (net (code "91") (name "unconnected-(U$1-S7B-Pad2)") (class "Default")
      (node (ref "U$1") (pin "2") (pinfunction "S7B_2") (pintype "bidirectional"))
    )
    (net (code "92") (name "unconnected-(U$1-S8A-Pad24)") (class "Default")
      (node (ref "U$1") (pin "24") (pinfunction "S8A_24") (pintype "bidirectional"))
    )
    (net (code "93") (name "unconnected-(U$1-S8B-Pad1)") (class "Default")
      (node (ref "U$1") (pin "1") (pinfunction "S8B_1") (pintype "bidirectional"))
    )
    (net (code "94") (name "unconnected-(U3-NC-Pad32)") (class "Default")
      (node (ref "U3") (pin "32") (pinfunction "NC_32") (pintype "passive"))
    )
    (net (code "95") (name "unconnected-(U3-NC_2-Pad12)") (class "Default")
      (node (ref "U3") (pin "12") (pinfunction "NC_2_12") (pintype "passive"))
    )
    (net (code "96") (name "unconnected-(U3-NC_3-Pad13)") (class "Default")
      (node (ref "U3") (pin "13") (pinfunction "NC_3_13") (pintype "passive"))
    )
    (net (code "97") (name "unconnected-(U3-NC_4-Pad26)") (class "Default")
      (node (ref "U3") (pin "26") (pinfunction "NC_4_26") (pintype "passive"))
    )
    (net (code "98") (name "unconnected-(U3-NC_5-Pad27)") (class "Default")
      (node (ref "U3") (pin "27") (pinfunction "NC_5_27") (pintype "passive"))
    )
    (net (code "99") (name "unconnected-(U3-NC_6-Pad28)") (class "Default")
      (node (ref "U3") (pin "28") (pinfunction "NC_6_28") (pintype "passive"))
    )
    (net (code "100") (name "unconnected-(U3-NC_7-Pad30)") (class "Default")
      (node (ref "U3") (pin "30") (pinfunction "NC_7_30") (pintype "passive"))
    )
    (net (code "101") (name "unconnected-(U3-PAD-Pad33)") (class "Default")
      (node (ref "U3") (pin "33") (pinfunction "PAD_33") (pintype "passive"))
    )
    (net (code "102") (name "unconnected-(U4-NC-Pad32)") (class "Default")
      (node (ref "U4") (pin "32") (pinfunction "NC_32") (pintype "passive"))
    )
    (net (code "103") (name "unconnected-(U4-NC_2-Pad12)") (class "Default")
      (node (ref "U4") (pin "12") (pinfunction "NC_2_12") (pintype "passive"))
    )
    (net (code "104") (name "unconnected-(U4-NC_3-Pad13)") (class "Default")
      (node (ref "U4") (pin "13") (pinfunction "NC_3_13") (pintype "passive"))
    )
    (net (code "105") (name "unconnected-(U4-NC_4-Pad26)") (class "Default")
      (node (ref "U4") (pin "26") (pinfunction "NC_4_26") (pintype "passive"))
    )
    (net (code "106") (name "unconnected-(U4-NC_5-Pad27)") (class "Default")
      (node (ref "U4") (pin "27") (pinfunction "NC_5_27") (pintype "passive"))
    )
    (net (code "107") (name "unconnected-(U4-NC_6-Pad28)") (class "Default")
      (node (ref "U4") (pin "28") (pinfunction "NC_6_28") (pintype "passive"))
    )
    (net (code "108") (name "unconnected-(U4-NC_7-Pad30)") (class "Default")
      (node (ref "U4") (pin "30") (pinfunction "NC_7_30") (pintype "passive"))
    )
    (net (code "109") (name "unconnected-(U4-PAD-Pad33)") (class "Default")
      (node (ref "U4") (pin "33") (pinfunction "PAD_33") (pintype "passive"))
    )
  )
)
